# pvii-001.net
KiCad netlist of a schematic drawn in EAGLE
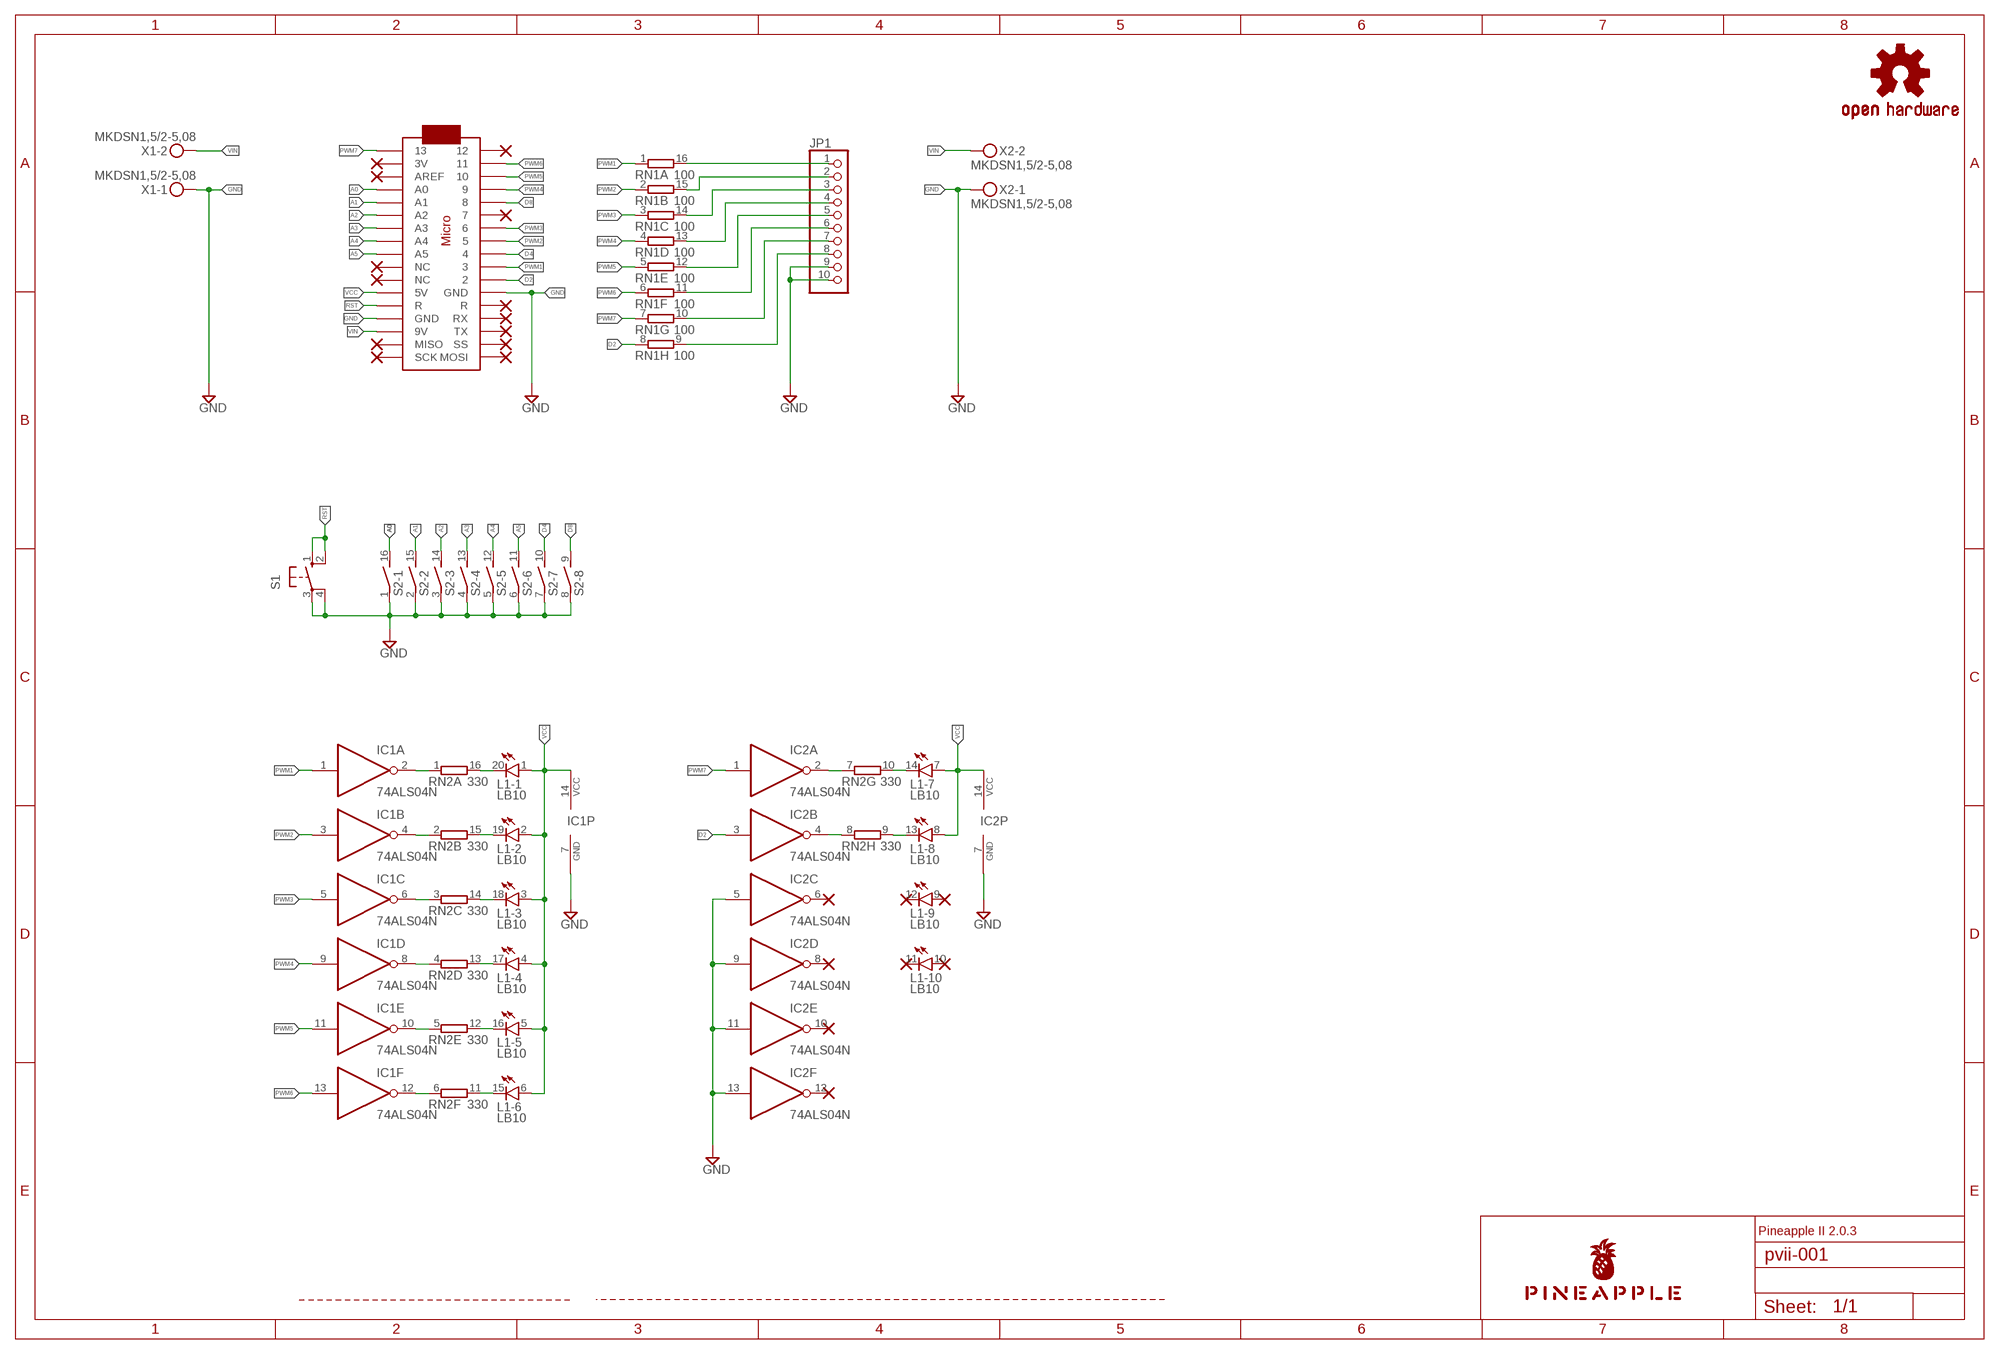
[diagram p0: schematic, sheet 1]

(export (version "E")
  (design (tool "Eeschema 10.0.6"))
  (components
    (comp (ref "IC1")
      (value "74ALS04N")
      (footprint "eagle-import:DIL14")
      (libsource (lib "eagle-import") (part "7404NALS"))
    )
    (comp (ref "IC2")
      (value "74ALS04N")
      (footprint "eagle-import:DIL14")
      (libsource (lib "eagle-import") (part "7404NALS"))
    )
    (comp (ref "JP1")
      (value "PINHD-1X10")
      (footprint "eagle-import:1X10")
      (libsource (lib "eagle-import") (part "PINHD-1X10"))
    )
    (comp (ref "L1")
      (value "LB10")
      (footprint "eagle-import:LB10")
      (libsource (lib "eagle-import") (part "LB10"))
    )
    (comp (ref "LOGO1")
      (value "OSHW-LOGOS-COPPER")
      (footprint "eagle-import:OSHW-LOGO-S_COPPER")
      (libsource (lib "eagle-import") (part "OSHW-LOGOS-COPPER"))
    )
    (comp (ref "MC1")
      (value "ARDUINOMICRO")
      (footprint "eagle-import:ARDUINOMICRO")
      (libsource (lib "eagle-import") (part "ARDUINOMICRO"))
    )
    (comp (ref "RN1")
      (value "100")
      (footprint "eagle-import:DIL16")
      (libsource (lib "eagle-import") (part "8R-N"))
    )
    (comp (ref "RN2")
      (value "330")
      (footprint "eagle-import:DIL16")
      (libsource (lib "eagle-import") (part "8R-N"))
    )
    (comp (ref "S1")
      (value "10-XX")
      (footprint "eagle-import:B3F-10XX")
      (fields (field (name "MPN") "B3F-1000"))
      (libsource (lib "eagle-import") (part "10-XX"))
    )
    (comp (ref "S2")
      (value "DIP08S")
      (footprint "eagle-import:DIP08S")
      (libsource (lib "eagle-import") (part "DIP08S"))
    )
    (comp (ref "U$1")
      (value "PINEAPPLE450_SILK")
      (footprint "eagle-import:PINEAPPLE450_SILK")
      (libsource (lib "eagle-import") (part "PINEAPPLE450_SILK"))
    )
    (comp (ref "X1")
      (value "MKDSN1,5/2-5,08")
      (footprint "eagle-import:MKDSN1,5_2-5,08")
      (libsource (lib "eagle-import") (part "MKDSN1,5/2-5,08"))
    )
    (comp (ref "X2")
      (value "MKDSN1,5/2-5,08")
      (footprint "eagle-import:MKDSN1,5_2-5,08")
      (libsource (lib "eagle-import") (part "MKDSN1,5/2-5,08"))
    )
  )
  (nets
    (net (code "1") (name "A0") (class "Default")
      (node (ref "MC1") (pin "P$31") (pinfunction "A0_P$31") (pintype "bidirectional"))
      (node (ref "S2") (pin "16") (pinfunction "2_16") (pintype "passive"))
    )
    (net (code "2") (name "A1") (class "Default")
      (node (ref "MC1") (pin "P$30") (pinfunction "A1_P$30") (pintype "bidirectional"))
      (node (ref "S2") (pin "15") (pinfunction "2_15") (pintype "passive"))
    )
    (net (code "3") (name "A2") (class "Default")
      (node (ref "MC1") (pin "P$29") (pinfunction "A2_P$29") (pintype "bidirectional"))
      (node (ref "S2") (pin "14") (pinfunction "2_14") (pintype "passive"))
    )
    (net (code "4") (name "A3") (class "Default")
      (node (ref "MC1") (pin "P$28") (pinfunction "A3_P$28") (pintype "bidirectional"))
      (node (ref "S2") (pin "13") (pinfunction "2_13") (pintype "passive"))
    )
    (net (code "5") (name "A4") (class "Default")
      (node (ref "MC1") (pin "P$27") (pinfunction "A4_P$27") (pintype "bidirectional"))
      (node (ref "S2") (pin "12") (pinfunction "2_12") (pintype "passive"))
    )
    (net (code "6") (name "A5") (class "Default")
      (node (ref "MC1") (pin "P$26") (pinfunction "A5_P$26") (pintype "bidirectional"))
      (node (ref "S2") (pin "11") (pinfunction "2_11") (pintype "passive"))
    )
    (net (code "7") (name "D2") (class "Default")
      (node (ref "IC2") (pin "3") (pinfunction "I_3") (pintype "input"))
      (node (ref "MC1") (pin "P$11") (pinfunction "2_P$11") (pintype "bidirectional"))
      (node (ref "RN1") (pin "8") (pinfunction "1_8") (pintype "passive"))
    )
    (net (code "8") (name "D4") (class "Default")
      (node (ref "MC1") (pin "P$9") (pinfunction "4_P$9") (pintype "bidirectional"))
      (node (ref "S2") (pin "10") (pinfunction "2_10") (pintype "passive"))
    )
    (net (code "9") (name "D8") (class "Default")
      (node (ref "MC1") (pin "P$5") (pinfunction "8_P$5") (pintype "bidirectional"))
      (node (ref "S2") (pin "9") (pinfunction "2_9") (pintype "passive"))
    )
    (net (code "10") (name "GND") (class "Default")
      (node (ref "IC1") (pin "7") (pinfunction "GND_7") (pintype "power_in"))
      (node (ref "IC2") (pin "11") (pinfunction "I_11") (pintype "input"))
      (node (ref "IC2") (pin "13") (pinfunction "I_13") (pintype "input"))
      (node (ref "IC2") (pin "5") (pinfunction "I_5") (pintype "input"))
      (node (ref "IC2") (pin "7") (pinfunction "GND_7") (pintype "power_in"))
      (node (ref "IC2") (pin "9") (pinfunction "I_9") (pintype "input"))
      (node (ref "JP1") (pin "10") (pinfunction "10_10") (pintype "passive"))
      (node (ref "JP1") (pin "9") (pinfunction "9_9") (pintype "passive"))
      (node (ref "MC1") (pin "P$12") (pinfunction "GND_P$12") (pintype "bidirectional"))
      (node (ref "MC1") (pin "P$21") (pinfunction "GND_P$21") (pintype "bidirectional"))
      (node (ref "S1") (pin "3") (pinfunction "P_3") (pintype "passive"))
      (node (ref "S1") (pin "4") (pinfunction "P1_4") (pintype "passive"))
      (node (ref "S2") (pin "1") (pinfunction "1_1") (pintype "passive"))
      (node (ref "S2") (pin "2") (pinfunction "1_2") (pintype "passive"))
      (node (ref "S2") (pin "3") (pinfunction "1_3") (pintype "passive"))
      (node (ref "S2") (pin "4") (pinfunction "1_4") (pintype "passive"))
      (node (ref "S2") (pin "5") (pinfunction "1_5") (pintype "passive"))
      (node (ref "S2") (pin "6") (pinfunction "1_6") (pintype "passive"))
      (node (ref "S2") (pin "7") (pinfunction "1_7") (pintype "passive"))
      (node (ref "S2") (pin "8") (pinfunction "1_8") (pintype "passive"))
      (node (ref "X1") (pin "1") (pinfunction "KL_1") (pintype "passive"))
      (node (ref "X2") (pin "1") (pinfunction "KL_1") (pintype "passive"))
    )
    (net (code "11") (name "Net-(IC1A-O)") (class "Default")
      (node (ref "IC1") (pin "2") (pinfunction "O_2") (pintype "output"))
      (node (ref "RN2") (pin "1") (pinfunction "1_1") (pintype "passive"))
    )
    (net (code "12") (name "Net-(IC1B-O)") (class "Default")
      (node (ref "IC1") (pin "4") (pinfunction "O_4") (pintype "output"))
      (node (ref "RN2") (pin "2") (pinfunction "1_2") (pintype "passive"))
    )
    (net (code "13") (name "Net-(IC1C-O)") (class "Default")
      (node (ref "IC1") (pin "6") (pinfunction "O_6") (pintype "output"))
      (node (ref "RN2") (pin "3") (pinfunction "1_3") (pintype "passive"))
    )
    (net (code "14") (name "Net-(IC1D-O)") (class "Default")
      (node (ref "IC1") (pin "8") (pinfunction "O_8") (pintype "output"))
      (node (ref "RN2") (pin "4") (pinfunction "1_4") (pintype "passive"))
    )
    (net (code "15") (name "Net-(IC1E-O)") (class "Default")
      (node (ref "IC1") (pin "10") (pinfunction "O_10") (pintype "output"))
      (node (ref "RN2") (pin "5") (pinfunction "1_5") (pintype "passive"))
    )
    (net (code "16") (name "Net-(IC1F-O)") (class "Default")
      (node (ref "IC1") (pin "12") (pinfunction "O_12") (pintype "output"))
      (node (ref "RN2") (pin "6") (pinfunction "1_6") (pintype "passive"))
    )
    (net (code "17") (name "Net-(IC2A-O)") (class "Default")
      (node (ref "IC2") (pin "2") (pinfunction "O_2") (pintype "output"))
      (node (ref "RN2") (pin "7") (pinfunction "1_7") (pintype "passive"))
    )
    (net (code "18") (name "Net-(IC2B-O)") (class "Default")
      (node (ref "IC2") (pin "4") (pinfunction "O_4") (pintype "output"))
      (node (ref "RN2") (pin "8") (pinfunction "1_8") (pintype "passive"))
    )
    (net (code "19") (name "Net-(L1A-C)") (class "Default")
      (node (ref "L1") (pin "20") (pinfunction "C_20") (pintype "passive"))
      (node (ref "RN2") (pin "16") (pinfunction "2_16") (pintype "passive"))
    )
    (net (code "20") (name "Net-(L1C-C)") (class "Default")
      (node (ref "L1") (pin "19") (pinfunction "C_19") (pintype "passive"))
      (node (ref "RN2") (pin "15") (pinfunction "2_15") (pintype "passive"))
    )
    (net (code "21") (name "Net-(L1D-C)") (class "Default")
      (node (ref "L1") (pin "18") (pinfunction "C_18") (pintype "passive"))
      (node (ref "RN2") (pin "14") (pinfunction "2_14") (pintype "passive"))
    )
    (net (code "22") (name "Net-(L1E-C)") (class "Default")
      (node (ref "L1") (pin "17") (pinfunction "C_17") (pintype "passive"))
      (node (ref "RN2") (pin "13") (pinfunction "2_13") (pintype "passive"))
    )
    (net (code "23") (name "Net-(L1F-C)") (class "Default")
      (node (ref "L1") (pin "16") (pinfunction "C_16") (pintype "passive"))
      (node (ref "RN2") (pin "12") (pinfunction "2_12") (pintype "passive"))
    )
    (net (code "24") (name "Net-(L1G-C)") (class "Default")
      (node (ref "L1") (pin "15") (pinfunction "C_15") (pintype "passive"))
      (node (ref "RN2") (pin "11") (pinfunction "2_11") (pintype "passive"))
    )
    (net (code "25") (name "Net-(L1H-C)") (class "Default")
      (node (ref "L1") (pin "14") (pinfunction "C_14") (pintype "passive"))
      (node (ref "RN2") (pin "10") (pinfunction "2_10") (pintype "passive"))
    )
    (net (code "26") (name "Net-(L1I-C)") (class "Default")
      (node (ref "L1") (pin "13") (pinfunction "C_13") (pintype "passive"))
      (node (ref "RN2") (pin "9") (pinfunction "2_9") (pintype "passive"))
    )
    (net (code "27") (name "Net-(RN1A-2)") (class "Default")
      (node (ref "JP1") (pin "1") (pinfunction "1_1") (pintype "passive"))
      (node (ref "RN1") (pin "16") (pinfunction "2_16") (pintype "passive"))
    )
    (net (code "28") (name "Net-(RN1B-2)") (class "Default")
      (node (ref "JP1") (pin "2") (pinfunction "2_2") (pintype "passive"))
      (node (ref "RN1") (pin "15") (pinfunction "2_15") (pintype "passive"))
    )
    (net (code "29") (name "Net-(RN1C-2)") (class "Default")
      (node (ref "JP1") (pin "3") (pinfunction "3_3") (pintype "passive"))
      (node (ref "RN1") (pin "14") (pinfunction "2_14") (pintype "passive"))
    )
    (net (code "30") (name "Net-(RN1D-2)") (class "Default")
      (node (ref "JP1") (pin "4") (pinfunction "4_4") (pintype "passive"))
      (node (ref "RN1") (pin "13") (pinfunction "2_13") (pintype "passive"))
    )
    (net (code "31") (name "Net-(RN1E-2)") (class "Default")
      (node (ref "JP1") (pin "5") (pinfunction "5_5") (pintype "passive"))
      (node (ref "RN1") (pin "12") (pinfunction "2_12") (pintype "passive"))
    )
    (net (code "32") (name "Net-(RN1F-2)") (class "Default")
      (node (ref "JP1") (pin "6") (pinfunction "6_6") (pintype "passive"))
      (node (ref "RN1") (pin "11") (pinfunction "2_11") (pintype "passive"))
    )
    (net (code "33") (name "Net-(RN1G-2)") (class "Default")
      (node (ref "JP1") (pin "7") (pinfunction "7_7") (pintype "passive"))
      (node (ref "RN1") (pin "10") (pinfunction "2_10") (pintype "passive"))
    )
    (net (code "34") (name "Net-(RN1H-2)") (class "Default")
      (node (ref "JP1") (pin "8") (pinfunction "8_8") (pintype "passive"))
      (node (ref "RN1") (pin "9") (pinfunction "2_9") (pintype "passive"))
    )
    (net (code "35") (name "PWM1") (class "Default")
      (node (ref "IC1") (pin "1") (pinfunction "I_1") (pintype "input"))
      (node (ref "MC1") (pin "P$10") (pinfunction "3_P$10") (pintype "bidirectional"))
      (node (ref "RN1") (pin "1") (pinfunction "1_1") (pintype "passive"))
    )
    (net (code "36") (name "PWM2") (class "Default")
      (node (ref "IC1") (pin "3") (pinfunction "I_3") (pintype "input"))
      (node (ref "MC1") (pin "P$8") (pinfunction "5_P$8") (pintype "bidirectional"))
      (node (ref "RN1") (pin "2") (pinfunction "1_2") (pintype "passive"))
    )
    (net (code "37") (name "PWM3") (class "Default")
      (node (ref "IC1") (pin "5") (pinfunction "I_5") (pintype "input"))
      (node (ref "MC1") (pin "P$7") (pinfunction "6_P$7") (pintype "bidirectional"))
      (node (ref "RN1") (pin "3") (pinfunction "1_3") (pintype "passive"))
    )
    (net (code "38") (name "PWM4") (class "Default")
      (node (ref "IC1") (pin "9") (pinfunction "I_9") (pintype "input"))
      (node (ref "MC1") (pin "P$4") (pinfunction "9_P$4") (pintype "bidirectional"))
      (node (ref "RN1") (pin "4") (pinfunction "1_4") (pintype "passive"))
    )
    (net (code "39") (name "PWM5") (class "Default")
      (node (ref "IC1") (pin "11") (pinfunction "I_11") (pintype "input"))
      (node (ref "MC1") (pin "P$3") (pinfunction "10_P$3") (pintype "bidirectional"))
      (node (ref "RN1") (pin "5") (pinfunction "1_5") (pintype "passive"))
    )
    (net (code "40") (name "PWM6") (class "Default")
      (node (ref "IC1") (pin "13") (pinfunction "I_13") (pintype "input"))
      (node (ref "MC1") (pin "P$2") (pinfunction "11_P$2") (pintype "bidirectional"))
      (node (ref "RN1") (pin "6") (pinfunction "1_6") (pintype "passive"))
    )
    (net (code "41") (name "PWM7") (class "Default")
      (node (ref "IC2") (pin "1") (pinfunction "I_1") (pintype "input"))
      (node (ref "MC1") (pin "P$34") (pinfunction "13_P$34") (pintype "bidirectional"))
      (node (ref "RN1") (pin "7") (pinfunction "1_7") (pintype "passive"))
    )
    (net (code "42") (name "RST") (class "Default")
      (node (ref "MC1") (pin "P$13") (pinfunction "R_P$13") (pintype "bidirectional"))
      (node (ref "S1") (pin "1") (pinfunction "S_1") (pintype "passive"))
      (node (ref "S1") (pin "2") (pinfunction "S1_2") (pintype "passive"))
    )
    (net (code "43") (name "VCC") (class "Default")
      (node (ref "IC1") (pin "14") (pinfunction "VCC_14") (pintype "power_in"))
      (node (ref "IC2") (pin "14") (pinfunction "VCC_14") (pintype "power_in"))
      (node (ref "L1") (pin "1") (pinfunction "A_1") (pintype "passive"))
      (node (ref "L1") (pin "2") (pinfunction "A_2") (pintype "passive"))
      (node (ref "L1") (pin "3") (pinfunction "A_3") (pintype "passive"))
      (node (ref "L1") (pin "4") (pinfunction "A_4") (pintype "passive"))
      (node (ref "L1") (pin "5") (pinfunction "A_5") (pintype "passive"))
      (node (ref "L1") (pin "6") (pinfunction "A_6") (pintype "passive"))
      (node (ref "L1") (pin "7") (pinfunction "A_7") (pintype "passive"))
      (node (ref "L1") (pin "8") (pinfunction "A_8") (pintype "passive"))
      (node (ref "MC1") (pin "P$23") (pinfunction "5V_P$23") (pintype "bidirectional"))
    )
    (net (code "44") (name "VIN") (class "Default")
      (node (ref "MC1") (pin "P$20") (pinfunction "9V_P$20") (pintype "bidirectional"))
      (node (ref "X1") (pin "2") (pinfunction "KL_2") (pintype "passive"))
      (node (ref "X2") (pin "2") (pinfunction "KL_2") (pintype "passive"))
    )
    (net (code "45") (name "unconnected-(IC2C-O-Pad6)") (class "Default")
      (node (ref "IC2") (pin "6") (pinfunction "O_6") (pintype "output"))
    )
    (net (code "46") (name "unconnected-(IC2D-O-Pad8)") (class "Default")
      (node (ref "IC2") (pin "8") (pinfunction "O_8") (pintype "output"))
    )
    (net (code "47") (name "unconnected-(IC2E-O-Pad10)") (class "Default")
      (node (ref "IC2") (pin "10") (pinfunction "O_10") (pintype "output"))
    )
    (net (code "48") (name "unconnected-(IC2F-O-Pad12)") (class "Default")
      (node (ref "IC2") (pin "12") (pinfunction "O_12") (pintype "output"))
    )
    (net (code "49") (name "unconnected-(L1B-A-Pad10)") (class "Default")
      (node (ref "L1") (pin "10") (pinfunction "A_10") (pintype "passive"))
    )
    (net (code "50") (name "unconnected-(L1B-C-Pad11)") (class "Default")
      (node (ref "L1") (pin "11") (pinfunction "C_11") (pintype "passive"))
    )
    (net (code "51") (name "unconnected-(L1J-A-Pad9)") (class "Default")
      (node (ref "L1") (pin "9") (pinfunction "A_9") (pintype "passive"))
    )
    (net (code "52") (name "unconnected-(L1J-C-Pad12)") (class "Default")
      (node (ref "L1") (pin "12") (pinfunction "C_12") (pintype "passive"))
    )
    (net (code "53") (name "unconnected-(MC1-3V-PadP$33)") (class "Default")
      (node (ref "MC1") (pin "P$33") (pinfunction "3V_P$33") (pintype "bidirectional"))
    )
    (net (code "54") (name "unconnected-(MC1-7-PadP$6)") (class "Default")
      (node (ref "MC1") (pin "P$6") (pinfunction "7_P$6") (pintype "bidirectional"))
    )
    (net (code "55") (name "unconnected-(MC1-12-PadP$1)") (class "Default")
      (node (ref "MC1") (pin "P$1") (pinfunction "12_P$1") (pintype "bidirectional"))
    )
    (net (code "56") (name "unconnected-(MC1-AREF-PadP$32)") (class "Default")
      (node (ref "MC1") (pin "P$32") (pinfunction "AREF_P$32") (pintype "bidirectional"))
    )
    (net (code "57") (name "unconnected-(MC1-MISO-PadP$19)") (class "Default")
      (node (ref "MC1") (pin "P$19") (pinfunction "MISO_P$19") (pintype "bidirectional"))
    )
    (net (code "58") (name "unconnected-(MC1-MOSI-PadP$17)") (class "Default")
      (node (ref "MC1") (pin "P$17") (pinfunction "MOSI_P$17") (pintype "bidirectional"))
    )
    (net (code "59") (name "unconnected-(MC1-NC-PadP$24)") (class "Default")
      (node (ref "MC1") (pin "P$24") (pinfunction "NC_P$24") (pintype "bidirectional"))
    )
    (net (code "60") (name "unconnected-(MC1-NC-PadP$25)") (class "Default")
      (node (ref "MC1") (pin "P$25") (pinfunction "NC_P$25") (pintype "bidirectional"))
    )
    (net (code "61") (name "unconnected-(MC1-R-PadP$22)") (class "Default")
      (node (ref "MC1") (pin "P$22") (pinfunction "R_P$22") (pintype "bidirectional"))
    )
    (net (code "62") (name "unconnected-(MC1-RX-PadP$14)") (class "Default")
      (node (ref "MC1") (pin "P$14") (pinfunction "RX_P$14") (pintype "bidirectional"))
    )
    (net (code "63") (name "unconnected-(MC1-SCK-PadP$18)") (class "Default")
      (node (ref "MC1") (pin "P$18") (pinfunction "SCK_P$18") (pintype "bidirectional"))
    )
    (net (code "64") (name "unconnected-(MC1-SS-PadP$16)") (class "Default")
      (node (ref "MC1") (pin "P$16") (pinfunction "SS_P$16") (pintype "bidirectional"))
    )
    (net (code "65") (name "unconnected-(MC1-TX-PadP$15)") (class "Default")
      (node (ref "MC1") (pin "P$15") (pinfunction "TX_P$15") (pintype "bidirectional"))
    )
  )
)
